# 02_memory.net
KiCad netlist of a schematic drawn in Altium Designer
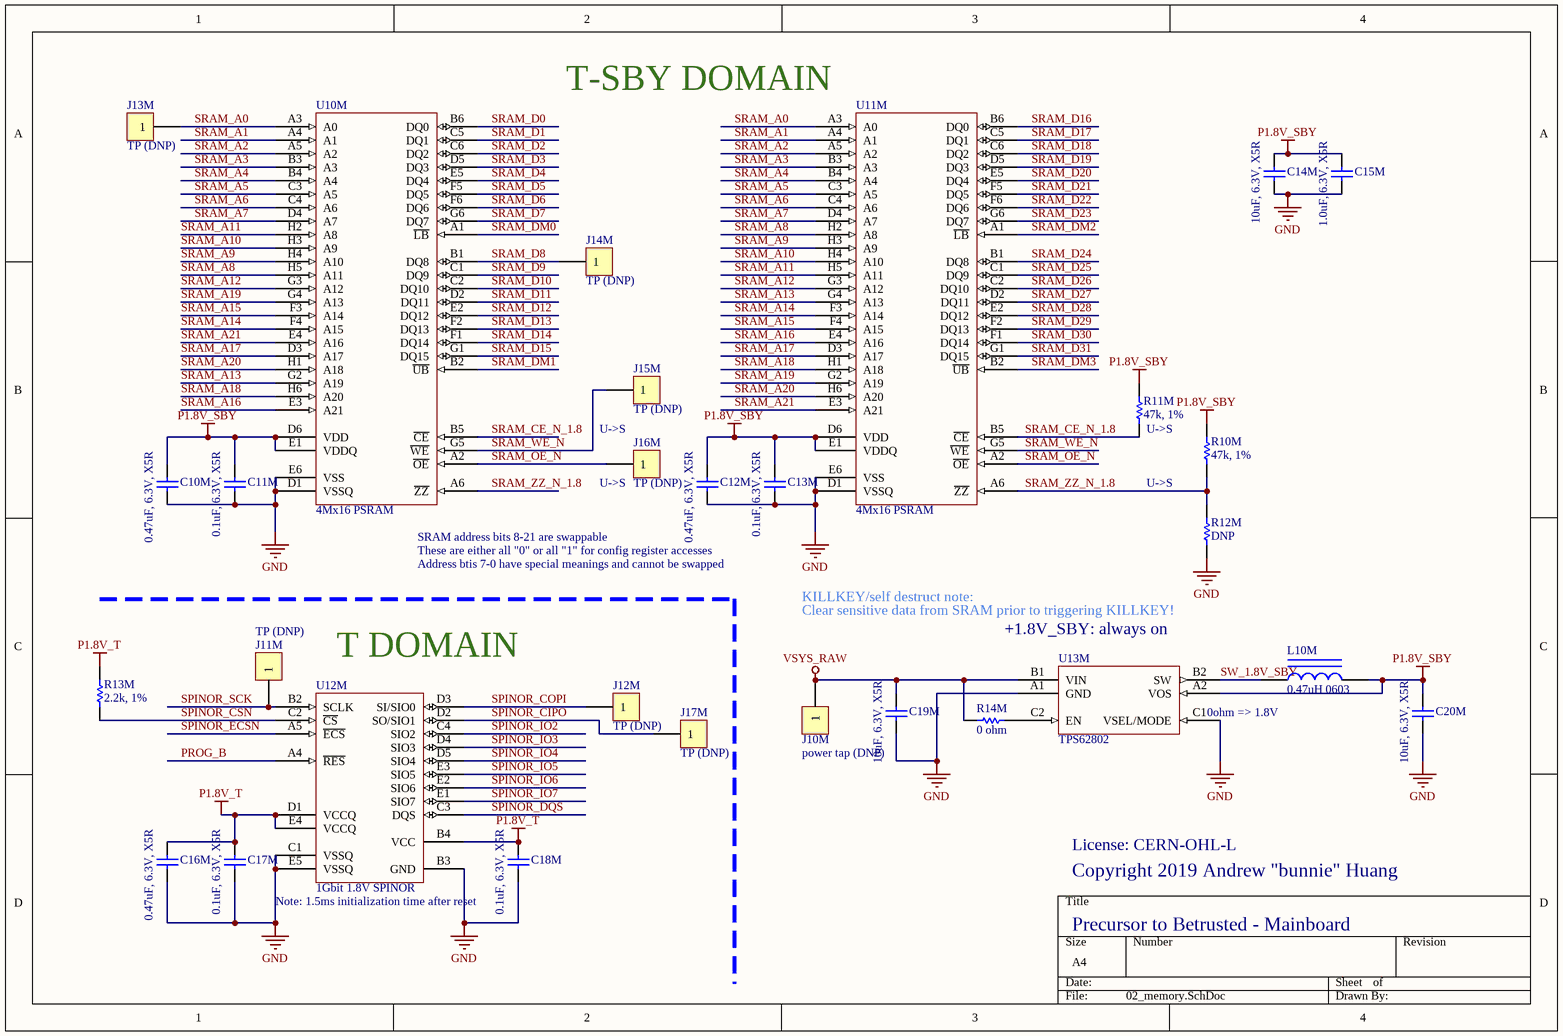
[diagram p0: 02_memory.SchDoc]

(export (version "E")
  (design (tool "Eeschema 10.0.6"))
  (components
    (comp (ref "C10M")
      (value "0.47uF, 6.3V, X5R")
      (footprint "B_CAP0201")
      (description "Capacitor (Semiconductor SIM Model)")
      (fields (field (name "MPN") "CL03A474KQ3NNNH"))
      (libsource (lib "Miscellaneous Devices") (part "Cap Semi"))
    )
    (comp (ref "C11M")
      (value "0.1uF, 6.3V, X5R")
      (footprint "B_CAP0201")
      (description "Capacitor (Semiconductor SIM Model)")
      (fields (field (name "MPN") "CL03A104KQ3NNNC"))
      (libsource (lib "Miscellaneous Devices") (part "Cap Semi"))
    )
    (comp (ref "C12M")
      (value "0.47uF, 6.3V, X5R")
      (footprint "B_CAP0201")
      (description "Capacitor (Semiconductor SIM Model)")
      (fields (field (name "MPN") "CL03A474KQ3NNNH"))
      (libsource (lib "Miscellaneous Devices") (part "Cap Semi"))
    )
    (comp (ref "C13M")
      (value "0.1uF, 6.3V, X5R")
      (footprint "B_CAP0201")
      (description "Capacitor (Semiconductor SIM Model)")
      (fields (field (name "MPN") "CL03A104KQ3NNNC"))
      (libsource (lib "Miscellaneous Devices") (part "Cap Semi"))
    )
    (comp (ref "C14M")
      (value "10uF, 6.3V, X5R")
      (footprint "B_CAP0603")
      (description "Capacitor (Semiconductor SIM Model)")
      (fields (field (name "MPN") "CL10A106MQ8NNNC"))
      (libsource (lib "Miscellaneous Devices") (part "Cap Semi"))
    )
    (comp (ref "C15M")
      (value "1.0uF, 6.3V, X5R")
      (footprint "B_CAP0201")
      (description "Capacitor (Semiconductor SIM Model)")
      (fields (field (name "MPN") "GRM033R60J105MEA2D"))
      (libsource (lib "Miscellaneous Devices") (part "Cap Semi"))
    )
    (comp (ref "C16M")
      (value "0.47uF, 6.3V, X5R")
      (footprint "B_CAP0201")
      (description "Capacitor (Semiconductor SIM Model)")
      (fields (field (name "MPN") "CL03A474KQ3NNNH"))
      (libsource (lib "Miscellaneous Devices") (part "Cap Semi"))
    )
    (comp (ref "C17M")
      (value "0.1uF, 6.3V, X5R")
      (footprint "B_CAP0201")
      (description "Capacitor (Semiconductor SIM Model)")
      (fields (field (name "MPN") "CL03A104KQ3NNNC"))
      (libsource (lib "Miscellaneous Devices") (part "Cap Semi"))
    )
    (comp (ref "C18M")
      (value "0.1uF, 6.3V, X5R")
      (footprint "B_CAP0201")
      (description "Capacitor (Semiconductor SIM Model)")
      (fields (field (name "MPN") "CL03A104KQ3NNNC"))
      (libsource (lib "Miscellaneous Devices") (part "Cap Semi"))
    )
    (comp (ref "C19M")
      (value "10uF, 6.3V, X5R")
      (footprint "B_CAP0603")
      (description "Capacitor (Semiconductor SIM Model)")
      (fields (field (name "MPN") "CL10A106MQ8NNNC"))
      (libsource (lib "Miscellaneous Devices") (part "Cap Semi"))
    )
    (comp (ref "C20M")
      (value "10uF, 6.3V, X5R")
      (footprint "B_CAP0603")
      (description "Capacitor (Semiconductor SIM Model)")
      (fields (field (name "MPN") "CL10A106MQ8NNNC"))
      (libsource (lib "Miscellaneous Devices") (part "Cap Semi"))
    )
    (comp (ref "J10M")
      (value "power tap (DNP)")
      (footprint "RESTAP-0603")
      (description "Connector")
      (fields (field (name "MPN") "DNP"))
      (libsource (lib "") (part "CON1_1"))
    )
    (comp (ref "J11M")
      (value "TP (DNP)")
      (footprint "TP_0.4x0.4_SMT")
      (description "Connector")
      (fields (field (name "MPN") "DNP"))
      (libsource (lib "") (part "CON1_3"))
    )
    (comp (ref "J12M")
      (value "TP (DNP)")
      (footprint "TP_0.4x0.4_SMT")
      (description "Connector")
      (fields (field (name "MPN") "DNP"))
      (libsource (lib "*") (part "CON1"))
    )
    (comp (ref "J13M")
      (value "TP (DNP)")
      (footprint "TP_0.4x0.4_SMT")
      (description "Connector")
      (fields (field (name "MPN") "DNP"))
      (libsource (lib "") (part "CON1_2"))
    )
    (comp (ref "J14M")
      (value "TP (DNP)")
      (footprint "TP_0.4x0.4_SMT")
      (description "Connector")
      (fields (field (name "MPN") "DNP"))
      (libsource (lib "*") (part "CON1"))
    )
    (comp (ref "J15M")
      (value "TP (DNP)")
      (footprint "TP_0.4x0.4_SMT")
      (description "Connector")
      (fields (field (name "MPN") "DNP"))
      (libsource (lib "*") (part "CON1"))
    )
    (comp (ref "J16M")
      (value "TP (DNP)")
      (footprint "TP_0.4x0.4_SMT")
      (description "Connector")
      (fields (field (name "MPN") "DNP"))
      (libsource (lib "*") (part "CON1"))
    )
    (comp (ref "J17M")
      (value "TP (DNP)")
      (footprint "TP_0.4x0.4_SMT")
      (description "Connector")
      (fields (field (name "MPN") "DNP"))
      (libsource (lib "*") (part "CON1"))
    )
    (comp (ref "L10M")
      (value "0.47uH 0603")
      (footprint "B_IND0603")
      (description "Magnetic-Core Inductor")
      (fields (field (name "MPN") "TFM160808ALC-R47MTAA"))
      (libsource (lib "Miscellaneous Devices") (part "Inductor Iron"))
    )
    (comp (ref "R10M")
      (value "47k, 1%")
      (footprint "B_RES0201")
      (description "Resistor")
      (fields (field (name "MPN") "ANY"))
      (libsource (lib "Miscellaneous Devices") (part "Res1"))
    )
    (comp (ref "R11M")
      (value "47k, 1%")
      (footprint "B_RES0201")
      (description "Resistor")
      (fields (field (name "MPN") "ANY"))
      (libsource (lib "Miscellaneous Devices") (part "Res1"))
    )
    (comp (ref "R12M")
      (value "DNP")
      (footprint "B_RES0201")
      (description "Resistor")
      (fields (field (name "MPN") "ANY"))
      (libsource (lib "Miscellaneous Devices") (part "Res1"))
    )
    (comp (ref "R13M")
      (value "2.2k, 1%")
      (footprint "B_RES0201")
      (description "Resistor")
      (fields (field (name "MPN") "ANY"))
      (libsource (lib "Miscellaneous Devices") (part "Res1"))
    )
    (comp (ref "R14M")
      (value "0 ohm")
      (footprint "B_RES0201")
      (description "Resistor")
      (fields (field (name "MPN") "ANY"))
      (libsource (lib "Miscellaneous Devices") (part "Res1"))
    )
    (comp (ref "U10M")
      (value "4Mx16 PSRAM")
      (footprint "BGA48C75P6X8_600X800X120")
      (fields (field (name "MPN") "IS66WVE4M16EALL-70BLI"))
      (libsource (lib "altium-import") (part "root_0_IS66WVE4M16_"))
    )
    (comp (ref "U11M")
      (value "4Mx16 PSRAM")
      (footprint "BGA48C75P6X8_600X800X120")
      (fields (field (name "MPN") "IS66WVE4M16EALL-70BLI"))
      (libsource (lib "altium-import") (part "root_0_IS66WVE4M16_"))
    )
    (comp (ref "U12M")
      (value "1Gbit 1.8V SPINOR")
      (footprint "BGA24C100P5X5_600X800X120")
      (description "1.8V 1Gbit x1/x8 OctaFlash SPINOR")
      (fields (field (name "MPN") "MX66UM1G45GXDI00"))
      (libsource (lib "commonsch-new") (part "MX66UM1G45G"))
    )
    (comp (ref "U13M")
      (value "TPS62802")
      (footprint "BGA6C35P2X3_70X105X40_NSMD")
      (description "Buck regulator, 4MHz, 0.6A, 1.8V-3.3V, low Iq")
      (fields (field (name "MPN") "TPS62802YKAR"))
      (libsource (lib "altium-import") (part "root_0_TPS62802_"))
    )
  )
  (nets
    (net (code "1") (name "/PROG_B") (class "Default")
      (node (ref "U12M") (pin "A4") (pinfunction "~{RES}_A4") (pintype "input"))
    )
    (net (code "2") (name "/SPINOR_CIPO") (class "Default")
      (node (ref "J17M") (pin "1") (pinfunction "1_1") (pintype "passive"))
      (node (ref "U12M") (pin "D2") (pinfunction "SO/SIO1_D2") (pintype "bidirectional"))
    )
    (net (code "3") (name "/SPINOR_COPI") (class "Default")
      (node (ref "J12M") (pin "1") (pinfunction "1_1") (pintype "passive"))
      (node (ref "U12M") (pin "D3") (pinfunction "SI/SIO0_D3") (pintype "bidirectional"))
    )
    (net (code "4") (name "/SPINOR_CSN") (class "Default")
      (node (ref "R13M") (pin "1") (pinfunction "1_1") (pintype "passive"))
      (node (ref "U12M") (pin "C2") (pinfunction "~{CS}_C2") (pintype "input"))
    )
    (net (code "5") (name "/SPINOR_DQS") (class "Default")
      (node (ref "U12M") (pin "C3") (pinfunction "DQS_C3") (pintype "bidirectional"))
    )
    (net (code "6") (name "/SPINOR_ECSN") (class "Default")
      (node (ref "U12M") (pin "A5") (pinfunction "~{ECS}_A5") (pintype "input"))
    )
    (net (code "7") (name "/SPINOR_IO2") (class "Default")
      (node (ref "U12M") (pin "C4") (pinfunction "SIO2_C4") (pintype "bidirectional"))
    )
    (net (code "8") (name "/SPINOR_IO3") (class "Default")
      (node (ref "U12M") (pin "D4") (pinfunction "SIO3_D4") (pintype "bidirectional"))
    )
    (net (code "9") (name "/SPINOR_IO4") (class "Default")
      (node (ref "U12M") (pin "D5") (pinfunction "SIO4_D5") (pintype "bidirectional"))
    )
    (net (code "10") (name "/SPINOR_IO5") (class "Default")
      (node (ref "U12M") (pin "E3") (pinfunction "SIO5_E3") (pintype "bidirectional"))
    )
    (net (code "11") (name "/SPINOR_IO6") (class "Default")
      (node (ref "U12M") (pin "E2") (pinfunction "SIO6_E2") (pintype "bidirectional"))
    )
    (net (code "12") (name "/SPINOR_IO7") (class "Default")
      (node (ref "U12M") (pin "E1") (pinfunction "SIO7_E1") (pintype "bidirectional"))
    )
    (net (code "13") (name "/SPINOR_SCK") (class "Default")
      (node (ref "J11M") (pin "1") (pinfunction "1_1") (pintype "passive"))
      (node (ref "U12M") (pin "B2") (pinfunction "SCLK_B2") (pintype "input"))
    )
    (net (code "14") (name "/SRAM_A0") (class "Default")
      (node (ref "J13M") (pin "1") (pinfunction "1_1") (pintype "passive"))
      (node (ref "U10M") (pin "A3") (pinfunction "A0_A3") (pintype "input"))
      (node (ref "U11M") (pin "A3") (pinfunction "A0_A3") (pintype "input"))
    )
    (net (code "15") (name "/SRAM_A1") (class "Default")
      (node (ref "U10M") (pin "A4") (pinfunction "A1_A4") (pintype "input"))
      (node (ref "U11M") (pin "A4") (pinfunction "A1_A4") (pintype "input"))
    )
    (net (code "16") (name "/SRAM_A2") (class "Default")
      (node (ref "U10M") (pin "A5") (pinfunction "A2_A5") (pintype "input"))
      (node (ref "U11M") (pin "A5") (pinfunction "A2_A5") (pintype "input"))
    )
    (net (code "17") (name "/SRAM_A3") (class "Default")
      (node (ref "U10M") (pin "B3") (pinfunction "A3_B3") (pintype "input"))
      (node (ref "U11M") (pin "B3") (pinfunction "A3_B3") (pintype "input"))
    )
    (net (code "18") (name "/SRAM_A4") (class "Default")
      (node (ref "U10M") (pin "B4") (pinfunction "A4_B4") (pintype "input"))
      (node (ref "U11M") (pin "B4") (pinfunction "A4_B4") (pintype "input"))
    )
    (net (code "19") (name "/SRAM_A5") (class "Default")
      (node (ref "U10M") (pin "C3") (pinfunction "A5_C3") (pintype "input"))
      (node (ref "U11M") (pin "C3") (pinfunction "A5_C3") (pintype "input"))
    )
    (net (code "20") (name "/SRAM_A6") (class "Default")
      (node (ref "U10M") (pin "C4") (pinfunction "A6_C4") (pintype "input"))
      (node (ref "U11M") (pin "C4") (pinfunction "A6_C4") (pintype "input"))
    )
    (net (code "21") (name "/SRAM_A7") (class "Default")
      (node (ref "U10M") (pin "D4") (pinfunction "A7_D4") (pintype "input"))
      (node (ref "U11M") (pin "D4") (pinfunction "A7_D4") (pintype "input"))
    )
    (net (code "22") (name "/SRAM_A8") (class "Default")
      (node (ref "U10M") (pin "H5") (pinfunction "A11_H5") (pintype "input"))
      (node (ref "U11M") (pin "H2") (pinfunction "A8_H2") (pintype "input"))
    )
    (net (code "23") (name "/SRAM_A9") (class "Default")
      (node (ref "U10M") (pin "H4") (pinfunction "A10_H4") (pintype "input"))
      (node (ref "U11M") (pin "H3") (pinfunction "A9_H3") (pintype "input"))
    )
    (net (code "24") (name "/SRAM_A10") (class "Default")
      (node (ref "U10M") (pin "H3") (pinfunction "A9_H3") (pintype "input"))
      (node (ref "U11M") (pin "H4") (pinfunction "A10_H4") (pintype "input"))
    )
    (net (code "25") (name "/SRAM_A11") (class "Default")
      (node (ref "U10M") (pin "H2") (pinfunction "A8_H2") (pintype "input"))
      (node (ref "U11M") (pin "H5") (pinfunction "A11_H5") (pintype "input"))
    )
    (net (code "26") (name "/SRAM_A12") (class "Default")
      (node (ref "U10M") (pin "G3") (pinfunction "A12_G3") (pintype "input"))
      (node (ref "U11M") (pin "G3") (pinfunction "A12_G3") (pintype "input"))
    )
    (net (code "27") (name "/SRAM_A13") (class "Default")
      (node (ref "U10M") (pin "G2") (pinfunction "A19_G2") (pintype "input"))
      (node (ref "U11M") (pin "G4") (pinfunction "A13_G4") (pintype "input"))
    )
    (net (code "28") (name "/SRAM_A14") (class "Default")
      (node (ref "U10M") (pin "F4") (pinfunction "A15_F4") (pintype "input"))
      (node (ref "U11M") (pin "F3") (pinfunction "A14_F3") (pintype "input"))
    )
    (net (code "29") (name "/SRAM_A15") (class "Default")
      (node (ref "U10M") (pin "F3") (pinfunction "A14_F3") (pintype "input"))
      (node (ref "U11M") (pin "F4") (pinfunction "A15_F4") (pintype "input"))
    )
    (net (code "30") (name "/SRAM_A16") (class "Default")
      (node (ref "U10M") (pin "E3") (pinfunction "A21_E3") (pintype "input"))
      (node (ref "U11M") (pin "E4") (pinfunction "A16_E4") (pintype "input"))
    )
    (net (code "31") (name "/SRAM_A17") (class "Default")
      (node (ref "U10M") (pin "D3") (pinfunction "A17_D3") (pintype "input"))
      (node (ref "U11M") (pin "D3") (pinfunction "A17_D3") (pintype "input"))
    )
    (net (code "32") (name "/SRAM_A18") (class "Default")
      (node (ref "U10M") (pin "H6") (pinfunction "A20_H6") (pintype "input"))
      (node (ref "U11M") (pin "H1") (pinfunction "A18_H1") (pintype "input"))
    )
    (net (code "33") (name "/SRAM_A19") (class "Default")
      (node (ref "U10M") (pin "G4") (pinfunction "A13_G4") (pintype "input"))
      (node (ref "U11M") (pin "G2") (pinfunction "A19_G2") (pintype "input"))
    )
    (net (code "34") (name "/SRAM_A20") (class "Default")
      (node (ref "U10M") (pin "H1") (pinfunction "A18_H1") (pintype "input"))
      (node (ref "U11M") (pin "H6") (pinfunction "A20_H6") (pintype "input"))
    )
    (net (code "35") (name "/SRAM_A21") (class "Default")
      (node (ref "U10M") (pin "E4") (pinfunction "A16_E4") (pintype "input"))
      (node (ref "U11M") (pin "E3") (pinfunction "A21_E3") (pintype "input"))
    )
    (net (code "36") (name "/SRAM_CE_N_1.8") (class "Default")
      (node (ref "R11M") (pin "2") (pinfunction "2_2") (pintype "passive"))
      (node (ref "U10M") (pin "B5") (pinfunction "~{CE}_B5") (pintype "input"))
      (node (ref "U11M") (pin "B5") (pinfunction "~{CE}_B5") (pintype "input"))
    )
    (net (code "37") (name "/SRAM_D0") (class "Default")
      (node (ref "U10M") (pin "B6") (pinfunction "DQ0_B6") (pintype "bidirectional"))
    )
    (net (code "38") (name "/SRAM_D1") (class "Default")
      (node (ref "U10M") (pin "C5") (pinfunction "DQ1_C5") (pintype "bidirectional"))
    )
    (net (code "39") (name "/SRAM_D2") (class "Default")
      (node (ref "U10M") (pin "C6") (pinfunction "DQ2_C6") (pintype "bidirectional"))
    )
    (net (code "40") (name "/SRAM_D3") (class "Default")
      (node (ref "U10M") (pin "D5") (pinfunction "DQ3_D5") (pintype "bidirectional"))
    )
    (net (code "41") (name "/SRAM_D4") (class "Default")
      (node (ref "U10M") (pin "E5") (pinfunction "DQ4_E5") (pintype "bidirectional"))
    )
    (net (code "42") (name "/SRAM_D5") (class "Default")
      (node (ref "U10M") (pin "F5") (pinfunction "DQ5_F5") (pintype "bidirectional"))
    )
    (net (code "43") (name "/SRAM_D6") (class "Default")
      (node (ref "U10M") (pin "F6") (pinfunction "DQ6_F6") (pintype "bidirectional"))
    )
    (net (code "44") (name "/SRAM_D7") (class "Default")
      (node (ref "U10M") (pin "G6") (pinfunction "DQ7_G6") (pintype "bidirectional"))
    )
    (net (code "45") (name "/SRAM_D8") (class "Default")
      (node (ref "J14M") (pin "1") (pinfunction "1_1") (pintype "passive"))
      (node (ref "U10M") (pin "B1") (pinfunction "DQ8_B1") (pintype "bidirectional"))
    )
    (net (code "46") (name "/SRAM_D9") (class "Default")
      (node (ref "U10M") (pin "C1") (pinfunction "DQ9_C1") (pintype "bidirectional"))
    )
    (net (code "47") (name "/SRAM_D10") (class "Default")
      (node (ref "U10M") (pin "C2") (pinfunction "DQ10_C2") (pintype "bidirectional"))
    )
    (net (code "48") (name "/SRAM_D11") (class "Default")
      (node (ref "U10M") (pin "D2") (pinfunction "DQ11_D2") (pintype "bidirectional"))
    )
    (net (code "49") (name "/SRAM_D12") (class "Default")
      (node (ref "U10M") (pin "E2") (pinfunction "DQ12_E2") (pintype "bidirectional"))
    )
    (net (code "50") (name "/SRAM_D13") (class "Default")
      (node (ref "U10M") (pin "F2") (pinfunction "DQ13_F2") (pintype "bidirectional"))
    )
    (net (code "51") (name "/SRAM_D14") (class "Default")
      (node (ref "U10M") (pin "F1") (pinfunction "DQ14_F1") (pintype "bidirectional"))
    )
    (net (code "52") (name "/SRAM_D15") (class "Default")
      (node (ref "U10M") (pin "G1") (pinfunction "DQ15_G1") (pintype "bidirectional"))
    )
    (net (code "53") (name "/SRAM_D16") (class "Default")
      (node (ref "U11M") (pin "B6") (pinfunction "DQ0_B6") (pintype "bidirectional"))
    )
    (net (code "54") (name "/SRAM_D17") (class "Default")
      (node (ref "U11M") (pin "C5") (pinfunction "DQ1_C5") (pintype "bidirectional"))
    )
    (net (code "55") (name "/SRAM_D18") (class "Default")
      (node (ref "U11M") (pin "C6") (pinfunction "DQ2_C6") (pintype "bidirectional"))
    )
    (net (code "56") (name "/SRAM_D19") (class "Default")
      (node (ref "U11M") (pin "D5") (pinfunction "DQ3_D5") (pintype "bidirectional"))
    )
    (net (code "57") (name "/SRAM_D20") (class "Default")
      (node (ref "U11M") (pin "E5") (pinfunction "DQ4_E5") (pintype "bidirectional"))
    )
    (net (code "58") (name "/SRAM_D21") (class "Default")
      (node (ref "U11M") (pin "F5") (pinfunction "DQ5_F5") (pintype "bidirectional"))
    )
    (net (code "59") (name "/SRAM_D22") (class "Default")
      (node (ref "U11M") (pin "F6") (pinfunction "DQ6_F6") (pintype "bidirectional"))
    )
    (net (code "60") (name "/SRAM_D23") (class "Default")
      (node (ref "U11M") (pin "G6") (pinfunction "DQ7_G6") (pintype "bidirectional"))
    )
    (net (code "61") (name "/SRAM_D24") (class "Default")
      (node (ref "U11M") (pin "B1") (pinfunction "DQ8_B1") (pintype "bidirectional"))
    )
    (net (code "62") (name "/SRAM_D25") (class "Default")
      (node (ref "U11M") (pin "C1") (pinfunction "DQ9_C1") (pintype "bidirectional"))
    )
    (net (code "63") (name "/SRAM_D26") (class "Default")
      (node (ref "U11M") (pin "C2") (pinfunction "DQ10_C2") (pintype "bidirectional"))
    )
    (net (code "64") (name "/SRAM_D27") (class "Default")
      (node (ref "U11M") (pin "D2") (pinfunction "DQ11_D2") (pintype "bidirectional"))
    )
    (net (code "65") (name "/SRAM_D28") (class "Default")
      (node (ref "U11M") (pin "E2") (pinfunction "DQ12_E2") (pintype "bidirectional"))
    )
    (net (code "66") (name "/SRAM_D29") (class "Default")
      (node (ref "U11M") (pin "F2") (pinfunction "DQ13_F2") (pintype "bidirectional"))
    )
    (net (code "67") (name "/SRAM_D30") (class "Default")
      (node (ref "U11M") (pin "F1") (pinfunction "DQ14_F1") (pintype "bidirectional"))
    )
    (net (code "68") (name "/SRAM_D31") (class "Default")
      (node (ref "U11M") (pin "G1") (pinfunction "DQ15_G1") (pintype "bidirectional"))
    )
    (net (code "69") (name "/SRAM_DM0") (class "Default")
      (node (ref "U10M") (pin "A1") (pinfunction "~{LB}_A1") (pintype "input"))
    )
    (net (code "70") (name "/SRAM_DM1") (class "Default")
      (node (ref "U10M") (pin "B2") (pinfunction "~{UB}_B2") (pintype "input"))
    )
    (net (code "71") (name "/SRAM_DM2") (class "Default")
      (node (ref "U11M") (pin "A1") (pinfunction "~{LB}_A1") (pintype "input"))
    )
    (net (code "72") (name "/SRAM_DM3") (class "Default")
      (node (ref "U11M") (pin "B2") (pinfunction "~{UB}_B2") (pintype "input"))
    )
    (net (code "73") (name "/SRAM_OE_N") (class "Default")
      (node (ref "J16M") (pin "1") (pinfunction "1_1") (pintype "passive"))
      (node (ref "U10M") (pin "A2") (pinfunction "~{OE}_A2") (pintype "input"))
      (node (ref "U11M") (pin "A2") (pinfunction "~{OE}_A2") (pintype "input"))
    )
    (net (code "74") (name "/SRAM_WE_N") (class "Default")
      (node (ref "J15M") (pin "1") (pinfunction "1_1") (pintype "passive"))
      (node (ref "U10M") (pin "G5") (pinfunction "~{WE}_G5") (pintype "input"))
      (node (ref "U11M") (pin "G5") (pinfunction "~{WE}_G5") (pintype "input"))
    )
    (net (code "75") (name "/SRAM_ZZ_N_1.8") (class "Default")
      (node (ref "R10M") (pin "2") (pinfunction "2_2") (pintype "passive"))
      (node (ref "R12M") (pin "1") (pinfunction "1_1") (pintype "passive"))
      (node (ref "U10M") (pin "A6") (pinfunction "~{ZZ}_A6") (pintype "input"))
      (node (ref "U11M") (pin "A6") (pinfunction "~{ZZ}_A6") (pintype "input"))
    )
    (net (code "76") (name "/SW_1.8V_SBY") (class "Default")
      (node (ref "L10M") (pin "1") (pinfunction "1_1") (pintype "passive"))
      (node (ref "U13M") (pin "B2") (pinfunction "SW_B2") (pintype "output"))
    )
    (net (code "77") (name "GND") (class "Default")
      (node (ref "C10M") (pin "2") (pinfunction "2_2") (pintype "passive"))
      (node (ref "C11M") (pin "2") (pinfunction "2_2") (pintype "passive"))
      (node (ref "C12M") (pin "2") (pinfunction "2_2") (pintype "passive"))
      (node (ref "C13M") (pin "2") (pinfunction "2_2") (pintype "passive"))
      (node (ref "C14M") (pin "2") (pinfunction "2_2") (pintype "passive"))
      (node (ref "C15M") (pin "1") (pinfunction "1_1") (pintype "passive"))
      (node (ref "C16M") (pin "2") (pinfunction "2_2") (pintype "passive"))
      (node (ref "C17M") (pin "2") (pinfunction "2_2") (pintype "passive"))
      (node (ref "C18M") (pin "2") (pinfunction "2_2") (pintype "passive"))
      (node (ref "C19M") (pin "2") (pinfunction "2_2") (pintype "passive"))
      (node (ref "C20M") (pin "2") (pinfunction "2_2") (pintype "passive"))
      (node (ref "R12M") (pin "2") (pinfunction "2_2") (pintype "passive"))
      (node (ref "U10M") (pin "D1") (pinfunction "VSSQ_D1") (pintype "power_in"))
      (node (ref "U10M") (pin "E6") (pinfunction "VSS_E6") (pintype "power_in"))
      (node (ref "U11M") (pin "D1") (pinfunction "VSSQ_D1") (pintype "power_in"))
      (node (ref "U11M") (pin "E6") (pinfunction "VSS_E6") (pintype "power_in"))
      (node (ref "U12M") (pin "B3") (pinfunction "GND_B3") (pintype "power_in"))
      (node (ref "U12M") (pin "C1") (pinfunction "VSSQ_C1") (pintype "power_in"))
      (node (ref "U12M") (pin "E5") (pinfunction "VSSQ_E5") (pintype "power_in"))
      (node (ref "U13M") (pin "A1") (pinfunction "GND_A1") (pintype "power_in"))
      (node (ref "U13M") (pin "C1") (pinfunction "VSEL/MODE_C1") (pintype "input"))
    )
    (net (code "78") (name "Net-(U13M-EN)") (class "Default")
      (node (ref "R14M") (pin "2") (pinfunction "2_2") (pintype "passive"))
      (node (ref "U13M") (pin "C2") (pinfunction "EN_C2") (pintype "input"))
    )
    (net (code "79") (name "P1.8V_SBY") (class "Default")
      (node (ref "C10M") (pin "1") (pinfunction "1_1") (pintype "passive"))
      (node (ref "C11M") (pin "1") (pinfunction "1_1") (pintype "passive"))
      (node (ref "C12M") (pin "1") (pinfunction "1_1") (pintype "passive"))
      (node (ref "C13M") (pin "1") (pinfunction "1_1") (pintype "passive"))
      (node (ref "C14M") (pin "1") (pinfunction "1_1") (pintype "passive"))
      (node (ref "C15M") (pin "2") (pinfunction "2_2") (pintype "passive"))
      (node (ref "C20M") (pin "1") (pinfunction "1_1") (pintype "passive"))
      (node (ref "L10M") (pin "2") (pinfunction "2_2") (pintype "passive"))
      (node (ref "R10M") (pin "1") (pinfunction "1_1") (pintype "passive"))
      (node (ref "R11M") (pin "1") (pinfunction "1_1") (pintype "passive"))
      (node (ref "U10M") (pin "D6") (pinfunction "VDD_D6") (pintype "power_in"))
      (node (ref "U10M") (pin "E1") (pinfunction "VDDQ_E1") (pintype "power_in"))
      (node (ref "U11M") (pin "D6") (pinfunction "VDD_D6") (pintype "power_in"))
      (node (ref "U11M") (pin "E1") (pinfunction "VDDQ_E1") (pintype "power_in"))
      (node (ref "U13M") (pin "A2") (pinfunction "VOS_A2") (pintype "input"))
    )
    (net (code "80") (name "P1.8V_T") (class "Default")
      (node (ref "C16M") (pin "1") (pinfunction "1_1") (pintype "passive"))
      (node (ref "C17M") (pin "1") (pinfunction "1_1") (pintype "passive"))
      (node (ref "C18M") (pin "1") (pinfunction "1_1") (pintype "passive"))
      (node (ref "R13M") (pin "2") (pinfunction "2_2") (pintype "passive"))
      (node (ref "U12M") (pin "B4") (pinfunction "VCC_B4") (pintype "power_in"))
      (node (ref "U12M") (pin "D1") (pinfunction "VCCQ_D1") (pintype "power_in"))
      (node (ref "U12M") (pin "E4") (pinfunction "VCCQ_E4") (pintype "power_in"))
    )
    (net (code "81") (name "VSYS_RAW") (class "Default")
      (node (ref "C19M") (pin "1") (pinfunction "1_1") (pintype "passive"))
      (node (ref "J10M") (pin "1") (pinfunction "1_1") (pintype "passive"))
      (node (ref "R14M") (pin "1") (pinfunction "1_1") (pintype "passive"))
      (node (ref "U13M") (pin "B1") (pinfunction "VIN_B1") (pintype "power_in"))
    )
  )
)
